# LED_Light_Drive.net
KiCad netlist of a schematic drawn in EAGLE
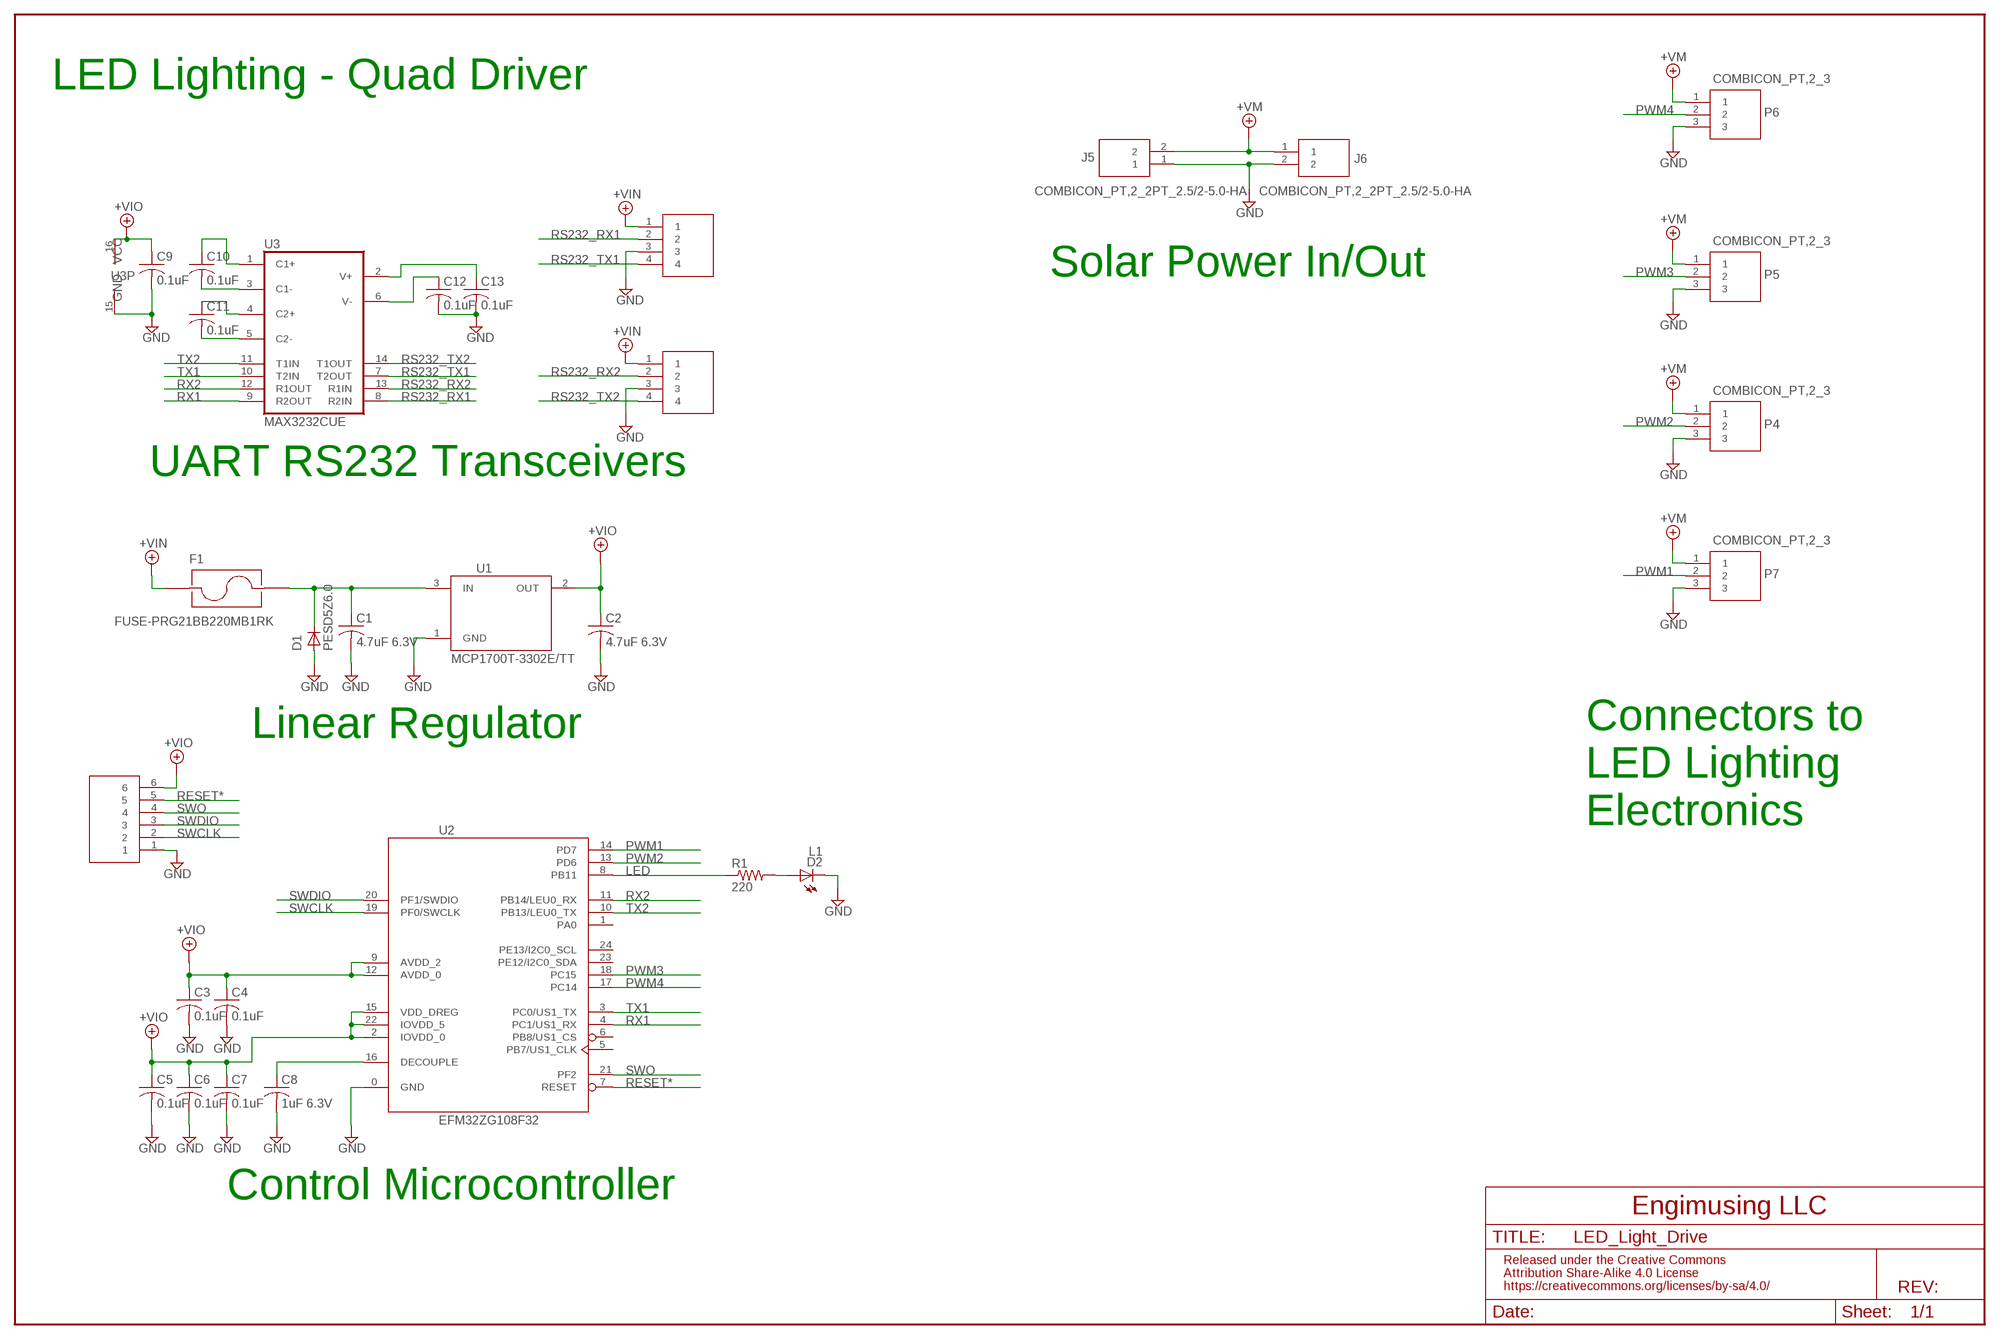
[diagram p0: schematic, sheet 1]

(export (version "E")
  (design (tool "Eeschema 10.0.6"))
  (components
    (comp (ref "C1")
      (value "4.7uF 6.3V")
      (footprint "eagle-import:C0603")
      (libsource (lib "eagle-import") (part "cc_rcl_C-USC0603"))
    )
    (comp (ref "C2")
      (value "4.7uF 6.3V")
      (footprint "eagle-import:C0603")
      (libsource (lib "eagle-import") (part "cc_rcl_C-USC0603"))
    )
    (comp (ref "C3")
      (value "0.1uF")
      (footprint "eagle-import:C0402")
      (libsource (lib "eagle-import") (part "cc_rcl_C-USC0402"))
    )
    (comp (ref "C4")
      (value "0.1uF")
      (footprint "eagle-import:C0402")
      (libsource (lib "eagle-import") (part "cc_rcl_C-USC0402"))
    )
    (comp (ref "C5")
      (value "0.1uF")
      (footprint "eagle-import:C0402")
      (libsource (lib "eagle-import") (part "cc_rcl_C-USC0402"))
    )
    (comp (ref "C6")
      (value "0.1uF")
      (footprint "eagle-import:C0402")
      (libsource (lib "eagle-import") (part "cc_rcl_C-USC0402"))
    )
    (comp (ref "C7")
      (value "0.1uF")
      (footprint "eagle-import:C0402")
      (libsource (lib "eagle-import") (part "cc_rcl_C-USC0402"))
    )
    (comp (ref "C8")
      (value "1uF 6.3V")
      (footprint "eagle-import:C0603")
      (libsource (lib "eagle-import") (part "C-USC0603"))
    )
    (comp (ref "C9")
      (value "0.1uF")
      (footprint "eagle-import:C0402")
      (libsource (lib "eagle-import") (part "cc_rcl_C-USC0402"))
    )
    (comp (ref "C10")
      (value "0.1uF")
      (footprint "eagle-import:C0402")
      (libsource (lib "eagle-import") (part "cc_rcl_C-USC0402"))
    )
    (comp (ref "C11")
      (value "0.1uF")
      (footprint "eagle-import:C0402")
      (libsource (lib "eagle-import") (part "cc_rcl_C-USC0402"))
    )
    (comp (ref "C12")
      (value "0.1uF")
      (footprint "eagle-import:C0402")
      (libsource (lib "eagle-import") (part "cc_rcl_C-USC0402"))
    )
    (comp (ref "C13")
      (value "0.1uF")
      (footprint "eagle-import:C0402")
      (libsource (lib "eagle-import") (part "cc_rcl_C-USC0402"))
    )
    (comp (ref "D1")
      (value "PESD5Z6.0")
      (footprint "eagle-import:SOD-523")
      (libsource (lib "eagle-import") (part "DIODESOD-523"))
    )
    (comp (ref "D2")
      (value "L1")
      (footprint "eagle-import:CHIP-LED0603")
      (libsource (lib "eagle-import") (part "LEDCHIP-LED0603"))
    )
    (comp (ref "F1")
      (value "FUSE-PRG21BB220MB1RK")
      (footprint "eagle-import:L0805_2.5")
      (libsource (lib "eagle-import") (part "FUSE-PRG21BB220MB1RK"))
    )
    (comp (ref "J5")
      (value "COMBICON_PT,2_2PT_2.5/2-5.0-HA")
      (footprint "eagle-import:PT_2,5_2-5.0-HA")
      (libsource (lib "eagle-import") (part "COMBICON_PT,2_2PT_2.5/2-5.0-HA"))
    )
    (comp (ref "J6")
      (value "COMBICON_PT,2_2PT_2.5/2-5.0-HA")
      (footprint "eagle-import:PT_2,5_2-5.0-HA")
      (libsource (lib "eagle-import") (part "COMBICON_PT,2_2PT_2.5/2-5.0-HA"))
    )
    (comp (ref "P1")
      (value "DF11-4_STRAIGHT_PIN")
      (footprint "eagle-import:DF11SP-4-H")
      (libsource (lib "eagle-import") (part "DF11-4_STRAIGHT_PIN"))
    )
    (comp (ref "P2")
      (value "DF11-4_STRAIGHT_PIN")
      (footprint "eagle-import:DF11SP-4-H")
      (libsource (lib "eagle-import") (part "DF11-4_STRAIGHT_PIN"))
    )
    (comp (ref "P3")
      (value "DF11-6_STRAIGHT_PIN")
      (footprint "eagle-import:DF11SP-6-H")
      (libsource (lib "eagle-import") (part "DF11-6_STRAIGHT_PIN"))
    )
    (comp (ref "P4")
      (value "COMBICON_PT,2_3")
      (footprint "eagle-import:PT_2,5_3-5,0-H")
      (libsource (lib "eagle-import") (part "COMBICON_PT,2_3"))
    )
    (comp (ref "P5")
      (value "COMBICON_PT,2_3")
      (footprint "eagle-import:PT_2,5_3-5,0-H")
      (libsource (lib "eagle-import") (part "COMBICON_PT,2_3"))
    )
    (comp (ref "P6")
      (value "COMBICON_PT,2_3")
      (footprint "eagle-import:PT_2,5_3-5,0-H")
      (libsource (lib "eagle-import") (part "COMBICON_PT,2_3"))
    )
    (comp (ref "P7")
      (value "COMBICON_PT,2_3")
      (footprint "eagle-import:PT_2,5_3-5,0-H")
      (libsource (lib "eagle-import") (part "COMBICON_PT,2_3"))
    )
    (comp (ref "R1")
      (value "220")
      (footprint "eagle-import:R0402")
      (libsource (lib "eagle-import") (part "R-USR0402"))
    )
    (comp (ref "U1")
      (value "MCP1700T-3302E/TT")
      (footprint "eagle-import:SOT23A")
      (libsource (lib "eagle-import") (part "MCP1700-3302E/TT"))
    )
    (comp (ref "U2")
      (value "EFM32ZG108F32")
      (footprint "eagle-import:QFN24_5X5")
      (libsource (lib "eagle-import") (part "EFM32ZG108F32"))
    )
    (comp (ref "U3")
      (value "MAX3232CUE")
      (footprint "eagle-import:TSSOP16")
      (fields (field (name "MF") "MAXIM") (field (name "MPN") "MAX3232CUE+"))
      (libsource (lib "eagle-import") (part "MAX3232UEC"))
    )
  )
  (nets
    (net (code "1") (name "+VIN") (class "Default")
      (node (ref "F1") (pin "2") (pinfunction "A_2") (pintype "passive"))
      (node (ref "P1") (pin "1") (pinfunction "1_1") (pintype "passive"))
      (node (ref "P2") (pin "1") (pinfunction "1_1") (pintype "passive"))
    )
    (net (code "2") (name "+VIO") (class "Default")
      (node (ref "C2") (pin "1") (pinfunction "1_1") (pintype "passive"))
      (node (ref "C3") (pin "1") (pinfunction "1_1") (pintype "passive"))
      (node (ref "C4") (pin "1") (pinfunction "1_1") (pintype "passive"))
      (node (ref "C5") (pin "1") (pinfunction "1_1") (pintype "passive"))
      (node (ref "C6") (pin "1") (pinfunction "1_1") (pintype "passive"))
      (node (ref "C7") (pin "1") (pinfunction "1_1") (pintype "passive"))
      (node (ref "C9") (pin "1") (pinfunction "1_1") (pintype "passive"))
      (node (ref "P3") (pin "6") (pinfunction "6_6") (pintype "passive"))
      (node (ref "U1") (pin "2") (pinfunction "OUT_2") (pintype "passive"))
      (node (ref "U2") (pin "12") (pinfunction "AVDD_0_12") (pintype "power_in"))
      (node (ref "U2") (pin "15") (pinfunction "VDD_DREG_15") (pintype "power_in"))
      (node (ref "U2") (pin "2") (pinfunction "IOVDD_0_2") (pintype "power_in"))
      (node (ref "U2") (pin "22") (pinfunction "IOVDD_5_22") (pintype "power_in"))
      (node (ref "U2") (pin "9") (pinfunction "AVDD_2_9") (pintype "power_in"))
      (node (ref "U3") (pin "16") (pinfunction "VCC_16") (pintype "power_in"))
    )
    (net (code "3") (name "+VM") (class "Default")
      (node (ref "J5") (pin "2") (pinfunction "2_2") (pintype "passive"))
      (node (ref "J6") (pin "1") (pinfunction "1_1") (pintype "passive"))
      (node (ref "P4") (pin "1") (pinfunction "1_1") (pintype "passive"))
      (node (ref "P5") (pin "1") (pinfunction "1_1") (pintype "passive"))
      (node (ref "P6") (pin "1") (pinfunction "1_1") (pintype "passive"))
      (node (ref "P7") (pin "1") (pinfunction "1_1") (pintype "passive"))
    )
    (net (code "4") (name "/LED") (class "Default")
      (node (ref "R1") (pin "1") (pinfunction "1_1") (pintype "passive"))
      (node (ref "U2") (pin "8") (pinfunction "PB11_8") (pintype "bidirectional"))
    )
    (net (code "5") (name "/PWM1") (class "Default")
      (node (ref "P7") (pin "2") (pinfunction "2_2") (pintype "passive"))
      (node (ref "U2") (pin "14") (pinfunction "PD7_14") (pintype "bidirectional"))
    )
    (net (code "6") (name "/PWM2") (class "Default")
      (node (ref "P4") (pin "2") (pinfunction "2_2") (pintype "passive"))
      (node (ref "U2") (pin "13") (pinfunction "PD6_13") (pintype "bidirectional"))
    )
    (net (code "7") (name "/PWM3") (class "Default")
      (node (ref "P5") (pin "2") (pinfunction "2_2") (pintype "passive"))
      (node (ref "U2") (pin "18") (pinfunction "PC15_18") (pintype "bidirectional"))
    )
    (net (code "8") (name "/PWM4") (class "Default")
      (node (ref "P6") (pin "2") (pinfunction "2_2") (pintype "passive"))
      (node (ref "U2") (pin "17") (pinfunction "PC14_17") (pintype "bidirectional"))
    )
    (net (code "9") (name "/RESET*") (class "Default")
      (node (ref "P3") (pin "5") (pinfunction "5_5") (pintype "passive"))
      (node (ref "U2") (pin "7") (pinfunction "RESET_7") (pintype "input"))
    )
    (net (code "10") (name "/RS232_RX1") (class "Default")
      (node (ref "P2") (pin "2") (pinfunction "2_2") (pintype "passive"))
      (node (ref "U3") (pin "8") (pinfunction "R2IN_8") (pintype "input"))
    )
    (net (code "11") (name "/RS232_RX2") (class "Default")
      (node (ref "P1") (pin "2") (pinfunction "2_2") (pintype "passive"))
      (node (ref "U3") (pin "13") (pinfunction "R1IN_13") (pintype "input"))
    )
    (net (code "12") (name "/RS232_TX1") (class "Default")
      (node (ref "P2") (pin "4") (pinfunction "4_4") (pintype "passive"))
      (node (ref "U3") (pin "7") (pinfunction "T2OUT_7") (pintype "output"))
    )
    (net (code "13") (name "/RS232_TX2") (class "Default")
      (node (ref "P1") (pin "4") (pinfunction "4_4") (pintype "passive"))
      (node (ref "U3") (pin "14") (pinfunction "T1OUT_14") (pintype "output"))
    )
    (net (code "14") (name "/RX1") (class "Default")
      (node (ref "U2") (pin "4") (pinfunction "PC1/US1_RX_4") (pintype "bidirectional"))
      (node (ref "U3") (pin "9") (pinfunction "R2OUT_9") (pintype "output"))
    )
    (net (code "15") (name "/RX2") (class "Default")
      (node (ref "U2") (pin "11") (pinfunction "PB14/LEU0_RX_11") (pintype "bidirectional"))
      (node (ref "U3") (pin "12") (pinfunction "R1OUT_12") (pintype "output"))
    )
    (net (code "16") (name "/SWCLK") (class "Default")
      (node (ref "P3") (pin "2") (pinfunction "2_2") (pintype "passive"))
      (node (ref "U2") (pin "19") (pinfunction "PF0/SWCLK_19") (pintype "bidirectional"))
    )
    (net (code "17") (name "/SWDIO") (class "Default")
      (node (ref "P3") (pin "3") (pinfunction "3_3") (pintype "passive"))
      (node (ref "U2") (pin "20") (pinfunction "PF1/SWDIO_20") (pintype "bidirectional"))
    )
    (net (code "18") (name "/SWO") (class "Default")
      (node (ref "P3") (pin "4") (pinfunction "4_4") (pintype "passive"))
      (node (ref "U2") (pin "21") (pinfunction "PF2_21") (pintype "bidirectional"))
    )
    (net (code "19") (name "/TX1") (class "Default")
      (node (ref "U2") (pin "3") (pinfunction "PC0/US1_TX_3") (pintype "bidirectional"))
      (node (ref "U3") (pin "10") (pinfunction "T2IN_10") (pintype "input"))
    )
    (net (code "20") (name "/TX2") (class "Default")
      (node (ref "U2") (pin "10") (pinfunction "PB13/LEU0_TX_10") (pintype "bidirectional"))
      (node (ref "U3") (pin "11") (pinfunction "T1IN_11") (pintype "input"))
    )
    (net (code "21") (name "GND") (class "Default")
      (node (ref "C1") (pin "2") (pinfunction "2_2") (pintype "passive"))
      (node (ref "C12") (pin "2") (pinfunction "2_2") (pintype "passive"))
      (node (ref "C13") (pin "2") (pinfunction "2_2") (pintype "passive"))
      (node (ref "C2") (pin "2") (pinfunction "2_2") (pintype "passive"))
      (node (ref "C3") (pin "2") (pinfunction "2_2") (pintype "passive"))
      (node (ref "C4") (pin "2") (pinfunction "2_2") (pintype "passive"))
      (node (ref "C5") (pin "2") (pinfunction "2_2") (pintype "passive"))
      (node (ref "C6") (pin "2") (pinfunction "2_2") (pintype "passive"))
      (node (ref "C7") (pin "2") (pinfunction "2_2") (pintype "passive"))
      (node (ref "C8") (pin "2") (pinfunction "2_2") (pintype "passive"))
      (node (ref "C9") (pin "2") (pinfunction "2_2") (pintype "passive"))
      (node (ref "D1") (pin "A") (pinfunction "A_A") (pintype "passive"))
      (node (ref "D2") (pin "C") (pinfunction "C_C") (pintype "passive"))
      (node (ref "J5") (pin "1") (pinfunction "1_1") (pintype "passive"))
      (node (ref "J6") (pin "2") (pinfunction "2_2") (pintype "passive"))
      (node (ref "P1") (pin "3") (pinfunction "3_3") (pintype "passive"))
      (node (ref "P2") (pin "3") (pinfunction "3_3") (pintype "passive"))
      (node (ref "P3") (pin "1") (pinfunction "1_1") (pintype "passive"))
      (node (ref "P4") (pin "3") (pinfunction "3_3") (pintype "passive"))
      (node (ref "P5") (pin "3") (pinfunction "3_3") (pintype "passive"))
      (node (ref "P6") (pin "3") (pinfunction "3_3") (pintype "passive"))
      (node (ref "P7") (pin "3") (pinfunction "3_3") (pintype "passive"))
      (node (ref "U1") (pin "1") (pinfunction "GND_1") (pintype "power_in"))
      (node (ref "U2") (pin "0") (pinfunction "GND_0") (pintype "power_in"))
      (node (ref "U3") (pin "15") (pinfunction "GND_15") (pintype "power_in"))
    )
    (net (code "22") (name "Net-(D1-C)") (class "Default")
      (node (ref "C1") (pin "1") (pinfunction "1_1") (pintype "passive"))
      (node (ref "D1") (pin "K") (pinfunction "C_K") (pintype "passive"))
      (node (ref "F1") (pin "1") (pinfunction "B_1") (pintype "passive"))
      (node (ref "U1") (pin "3") (pinfunction "IN_3") (pintype "power_in"))
    )
    (net (code "23") (name "Net-(D2-PadA)") (class "Default")
      (node (ref "D2") (pin "A") (pinfunction "A_A") (pintype "passive"))
      (node (ref "R1") (pin "2") (pinfunction "2_2") (pintype "passive"))
    )
    (net (code "24") (name "Net-(U2-DECOUPLE)") (class "Default")
      (node (ref "C8") (pin "1") (pinfunction "1_1") (pintype "passive"))
      (node (ref "U2") (pin "16") (pinfunction "DECOUPLE_16") (pintype "passive"))
    )
    (net (code "25") (name "Net-(U3A-C1+)") (class "Default")
      (node (ref "C10") (pin "1") (pinfunction "1_1") (pintype "passive"))
      (node (ref "U3") (pin "1") (pinfunction "C1+_1") (pintype "bidirectional"))
    )
    (net (code "26") (name "Net-(U3A-C1-)") (class "Default")
      (node (ref "C10") (pin "2") (pinfunction "2_2") (pintype "passive"))
      (node (ref "U3") (pin "3") (pinfunction "C1-_3") (pintype "bidirectional"))
    )
    (net (code "27") (name "Net-(U3A-C2+)") (class "Default")
      (node (ref "C11") (pin "1") (pinfunction "1_1") (pintype "passive"))
      (node (ref "U3") (pin "4") (pinfunction "C2+_4") (pintype "bidirectional"))
    )
    (net (code "28") (name "Net-(U3A-C2-)") (class "Default")
      (node (ref "C11") (pin "2") (pinfunction "2_2") (pintype "passive"))
      (node (ref "U3") (pin "5") (pinfunction "C2-_5") (pintype "bidirectional"))
    )
    (net (code "29") (name "Net-(U3A-V+)") (class "Default")
      (node (ref "C13") (pin "1") (pinfunction "1_1") (pintype "passive"))
      (node (ref "U3") (pin "2") (pinfunction "V+_2") (pintype "bidirectional"))
    )
    (net (code "30") (name "Net-(U3A-V-)") (class "Default")
      (node (ref "C12") (pin "1") (pinfunction "1_1") (pintype "passive"))
      (node (ref "U3") (pin "6") (pinfunction "V-_6") (pintype "bidirectional"))
    )
    (net (code "31") (name "unconnected-(U2-PA0-Pad1)") (class "Default")
      (node (ref "U2") (pin "1") (pinfunction "PA0_1") (pintype "bidirectional"))
    )
    (net (code "32") (name "unconnected-(U2-PB7{slash}US1_CLK-Pad5)") (class "Default")
      (node (ref "U2") (pin "5") (pinfunction "PB7/US1_CLK_5") (pintype "bidirectional"))
    )
    (net (code "33") (name "unconnected-(U2-PB8{slash}US1_CS-Pad6)") (class "Default")
      (node (ref "U2") (pin "6") (pinfunction "PB8/US1_CS_6") (pintype "bidirectional"))
    )
    (net (code "34") (name "unconnected-(U2-PE12{slash}I2C0_SDA-Pad23)") (class "Default")
      (node (ref "U2") (pin "23") (pinfunction "PE12/I2C0_SDA_23") (pintype "bidirectional"))
    )
    (net (code "35") (name "unconnected-(U2-PE13{slash}I2C0_SCL-Pad24)") (class "Default")
      (node (ref "U2") (pin "24") (pinfunction "PE13/I2C0_SCL_24") (pintype "bidirectional"))
    )
  )
)
